# I2C_Jog_Controller.net
KiCad netlist of a schematic drawn in Altium Designer
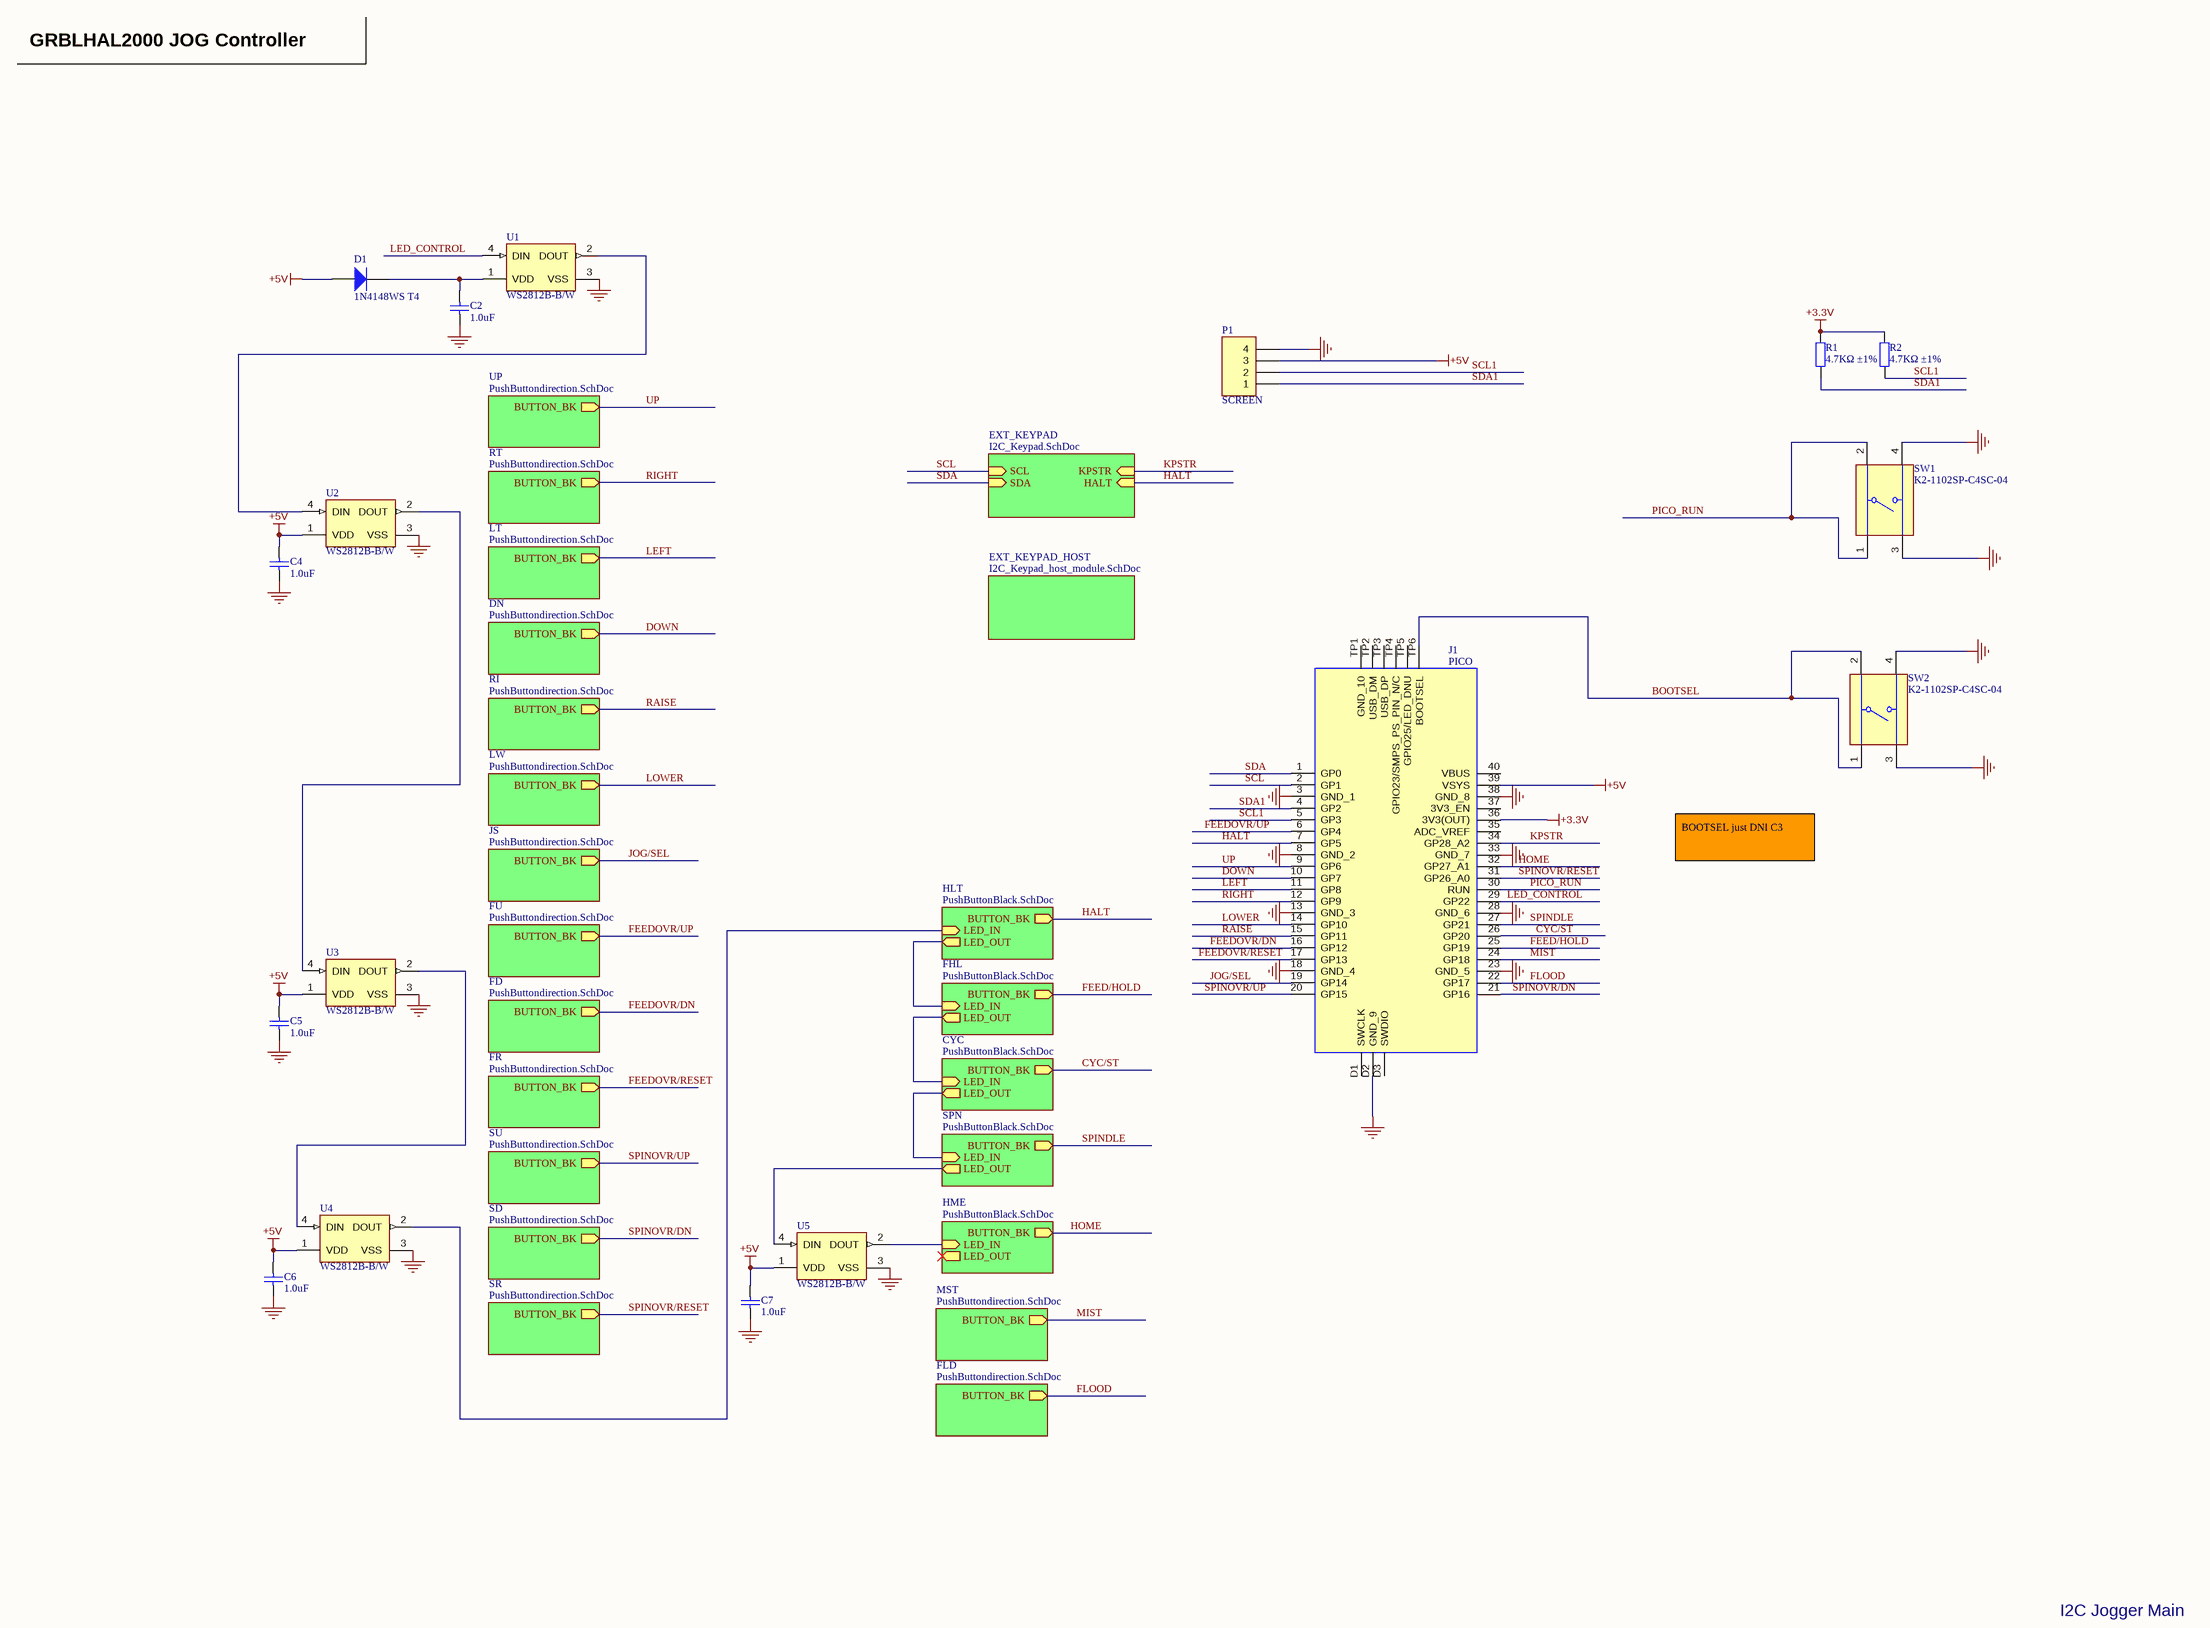
[diagram p0: I2C_Jog_Controller.SchDoc]

(export (version "E")
  (design (tool "Eeschema 10.0.6"))
  (components
    (comp (ref "C2")
      (value "1.0uF")
      (footprint "0402_C")
      (description "Chip capacitor")
      (fields
        (field (name "MANUFACTURER") "Samsung Electro-Mechanics")
        (field (name "PARTNUMBER") "CL05A105KA5NQNC")
      )
      (libsource (lib "Cap") (part "0402 1.0uF (105) 10% 25V"))
    )
    (comp (ref "C4")
      (value "1.0uF")
      (footprint "0402_C")
      (description "Chip capacitor")
      (fields
        (field (name "MANUFACTURER") "Samsung Electro-Mechanics")
        (field (name "PARTNUMBER") "CL05A105KA5NQNC")
      )
      (libsource (lib "Cap") (part "0402 1.0uF (105) 10% 25V"))
    )
    (comp (ref "C5")
      (value "1.0uF")
      (footprint "0402_C")
      (description "Chip capacitor")
      (fields
        (field (name "MANUFACTURER") "Samsung Electro-Mechanics")
        (field (name "PARTNUMBER") "CL05A105KA5NQNC")
      )
      (libsource (lib "Cap") (part "0402 1.0uF (105) 10% 25V"))
    )
    (comp (ref "C6")
      (value "1.0uF")
      (footprint "0402_C")
      (description "Chip capacitor")
      (fields
        (field (name "MANUFACTURER") "Samsung Electro-Mechanics")
        (field (name "PARTNUMBER") "CL05A105KA5NQNC")
      )
      (libsource (lib "Cap") (part "0402 1.0uF (105) 10% 25V"))
    )
    (comp (ref "C7")
      (value "1.0uF")
      (footprint "0402_C")
      (description "Chip capacitor")
      (fields
        (field (name "MANUFACTURER") "Samsung Electro-Mechanics")
        (field (name "PARTNUMBER") "CL05A105KA5NQNC")
      )
      (libsource (lib "Cap") (part "0402 1.0uF (105) 10% 25V"))
    )
    (comp (ref "D1")
      (value "1N4148WS T4")
      (footprint "SOD-323")
      (description "二极管")
      (libsource (lib "Diode") (part "SOD-323 1N4148WS T4"))
    )
    (comp (ref "J1")
      (value "PICO")
      (footprint "SamacSys:PICO")
      (description "Connector")
      (libsource (lib "I2C_Jog_Controller") (part "PICO"))
    )
    (comp (ref "P1")
      (value "SCREEN")
      (footprint "HDR1X4")
      (description "Header, 4-Pin")
      (fields (field (name "PUBLISHER") "Altium Limited"))
      (libsource (lib "Miscellaneous Connectors") (part "Header 4"))
    )
    (comp (ref "R1")
      (value "4.7KΩ ±1%")
      (footprint "0402_R")
      (description "Chip resistor")
      (fields (field (name "MANUFACTURER") "Uniroyal Elec") (field (name "PARTNUMBER") "0402WGF4701TCE"))
      (libsource (lib "RES") (part "0402 4.7K (4701) 1%"))
    )
    (comp (ref "R2")
      (value "4.7KΩ ±1%")
      (footprint "0402_R")
      (description "Chip resistor")
      (fields (field (name "MANUFACTURER") "Uniroyal Elec") (field (name "PARTNUMBER") "0402WGF4701TCE"))
      (libsource (lib "RES") (part "0402 4.7K (4701) 1%"))
    )
    (comp (ref "SW1")
      (value "K2-1102SP-C4SC-04")
      (footprint "TECO-FSM4JSMATR_V")
      (description "Top Actuated 50mA @ 12VDC Round Button SPST 6*6mm Tactile Switches ROHS")
      (libsource (lib "Altium Content Vault") (part "SW-SPST-4_A"))
    )
    (comp (ref "SW2")
      (value "K2-1102SP-C4SC-04")
      (footprint "TECO-FSM4JSMATR_V")
      (description "Top Actuated 50mA @ 12VDC Round Button SPST 6*6mm Tactile Switches ROHS")
      (libsource (lib "Altium Content Vault") (part "SW-SPST-4_A"))
    )
    (comp (ref "U1")
      (value "WS2812B-B/W")
      (footprint "ADA-RGB-1655_V")
      (fields (field (name "MANUFACTURER") "Worldsemi"))
      (libsource (lib "Altium Content Vault") (part "ADA-RGB-1655-4"))
    )
    (comp (ref "U2")
      (value "WS2812B-B/W")
      (footprint "ADA-RGB-1655_V")
      (fields (field (name "MANUFACTURER") "Worldsemi"))
      (libsource (lib "Altium Content Vault") (part "ADA-RGB-1655-4"))
    )
    (comp (ref "U3")
      (value "WS2812B-B/W")
      (footprint "ADA-RGB-1655_V")
      (fields (field (name "MANUFACTURER") "Worldsemi"))
      (libsource (lib "Altium Content Vault") (part "ADA-RGB-1655-4"))
    )
    (comp (ref "U4")
      (value "WS2812B-B/W")
      (footprint "ADA-RGB-1655_V")
      (fields (field (name "MANUFACTURER") "Worldsemi"))
      (libsource (lib "Altium Content Vault") (part "ADA-RGB-1655-4"))
    )
    (comp (ref "U5")
      (value "WS2812B-B/W")
      (footprint "ADA-RGB-1655_V")
      (fields (field (name "MANUFACTURER") "Worldsemi"))
      (libsource (lib "Altium Content Vault") (part "ADA-RGB-1655-4"))
    )
  )
  (nets
    (net (code "1") (name "+3.3V") (class "Default")
      (node (ref "J1") (pin "36") (pinfunction "3V3(OUT)_36") (pintype "passive"))
      (node (ref "R1") (pin "2") (pinfunction "2_2") (pintype "passive"))
      (node (ref "R2") (pin "2") (pinfunction "2_2") (pintype "passive"))
    )
    (net (code "2") (name "+5V") (class "Default")
      (node (ref "C4") (pin "2") (pinfunction "2_2") (pintype "passive"))
      (node (ref "C5") (pin "2") (pinfunction "2_2") (pintype "passive"))
      (node (ref "C6") (pin "2") (pinfunction "2_2") (pintype "passive"))
      (node (ref "C7") (pin "2") (pinfunction "2_2") (pintype "passive"))
      (node (ref "D1") (pin "1") (pinfunction "A_1") (pintype "passive"))
      (node (ref "J1") (pin "39") (pinfunction "VSYS_39") (pintype "passive"))
      (node (ref "P1") (pin "3") (pinfunction "3_3") (pintype "passive"))
      (node (ref "U2") (pin "1") (pinfunction "VDD_1") (pintype "power_in"))
      (node (ref "U3") (pin "1") (pinfunction "VDD_1") (pintype "power_in"))
      (node (ref "U4") (pin "1") (pinfunction "VDD_1") (pintype "power_in"))
      (node (ref "U5") (pin "1") (pinfunction "VDD_1") (pintype "power_in"))
    )
    (net (code "3") (name "/BOOTSEL") (class "Default")
      (node (ref "J1") (pin "TP6") (pinfunction "BOOTSEL_TP6") (pintype "passive"))
      (node (ref "SW2") (pin "1") (pinfunction "1_1") (pintype "passive"))
      (node (ref "SW2") (pin "2") (pinfunction "2_2") (pintype "passive"))
    )
    (net (code "4") (name "/CYC{slash}ST") (class "Default")
      (node (ref "J1") (pin "26") (pinfunction "GP20_26") (pintype "passive"))
    )
    (net (code "5") (name "/DOWN") (class "Default")
      (node (ref "J1") (pin "10") (pinfunction "GP7_10") (pintype "passive"))
    )
    (net (code "6") (name "/FEEDOVR{slash}DN") (class "Default")
      (node (ref "J1") (pin "16") (pinfunction "GP12_16") (pintype "passive"))
    )
    (net (code "7") (name "/FEEDOVR{slash}RESET") (class "Default")
      (node (ref "J1") (pin "17") (pinfunction "GP13_17") (pintype "passive"))
    )
    (net (code "8") (name "/FEEDOVR{slash}UP") (class "Default")
      (node (ref "J1") (pin "6") (pinfunction "GP4_6") (pintype "passive"))
    )
    (net (code "9") (name "/FEED{slash}HOLD") (class "Default")
      (node (ref "J1") (pin "25") (pinfunction "GP19_25") (pintype "passive"))
    )
    (net (code "10") (name "/FLOOD") (class "Default")
      (node (ref "J1") (pin "22") (pinfunction "GP17_22") (pintype "passive"))
    )
    (net (code "11") (name "/HALT") (class "Default")
      (node (ref "J1") (pin "7") (pinfunction "GP5_7") (pintype "passive"))
    )
    (net (code "12") (name "/HOME") (class "Default")
      (node (ref "J1") (pin "32") (pinfunction "GP27_A1_32") (pintype "passive"))
    )
    (net (code "13") (name "/JOG{slash}SEL") (class "Default")
      (node (ref "J1") (pin "19") (pinfunction "GP14_19") (pintype "passive"))
    )
    (net (code "14") (name "/KPSTR") (class "Default")
      (node (ref "J1") (pin "34") (pinfunction "GP28_A2_34") (pintype "passive"))
    )
    (net (code "15") (name "/LED_CONTROL") (class "Default")
      (node (ref "J1") (pin "29") (pinfunction "GP22_29") (pintype "passive"))
      (node (ref "U1") (pin "4") (pinfunction "DIN_4") (pintype "input"))
    )
    (net (code "16") (name "/LED_IN") (class "Default")
      (node (ref "U5") (pin "2") (pinfunction "DOUT_2") (pintype "output"))
    )
    (net (code "17") (name "/LED_IN_1") (class "Default")
      (node (ref "U4") (pin "2") (pinfunction "DOUT_2") (pintype "output"))
    )
    (net (code "19") (name "/LED_OUT_1") (class "Default")
      (node (ref "U5") (pin "4") (pinfunction "DIN_4") (pintype "input"))
    )
    (net (code "23") (name "/LEFT") (class "Default")
      (node (ref "J1") (pin "11") (pinfunction "GP8_11") (pintype "passive"))
    )
    (net (code "24") (name "/LOWER") (class "Default")
      (node (ref "J1") (pin "14") (pinfunction "GP10_14") (pintype "passive"))
    )
    (net (code "25") (name "/MIST") (class "Default")
      (node (ref "J1") (pin "24") (pinfunction "GP18_24") (pintype "passive"))
    )
    (net (code "26") (name "/PICO_RUN") (class "Default")
      (node (ref "J1") (pin "30") (pinfunction "RUN_30") (pintype "passive"))
      (node (ref "SW1") (pin "1") (pinfunction "1_1") (pintype "passive"))
      (node (ref "SW1") (pin "2") (pinfunction "2_2") (pintype "passive"))
    )
    (net (code "27") (name "/RAISE") (class "Default")
      (node (ref "J1") (pin "15") (pinfunction "GP11_15") (pintype "passive"))
    )
    (net (code "28") (name "/RIGHT") (class "Default")
      (node (ref "J1") (pin "12") (pinfunction "GP9_12") (pintype "passive"))
    )
    (net (code "29") (name "/SCL") (class "Default")
      (node (ref "J1") (pin "2") (pinfunction "GP1_2") (pintype "passive"))
    )
    (net (code "30") (name "/SCL1") (class "Default")
      (node (ref "J1") (pin "5") (pinfunction "GP3_5") (pintype "passive"))
      (node (ref "P1") (pin "2") (pinfunction "2_2") (pintype "passive"))
      (node (ref "R2") (pin "1") (pinfunction "1_1") (pintype "passive"))
    )
    (net (code "31") (name "/SDA") (class "Default")
      (node (ref "J1") (pin "1") (pinfunction "GP0_1") (pintype "passive"))
    )
    (net (code "32") (name "/SDA1") (class "Default")
      (node (ref "J1") (pin "4") (pinfunction "GP2_4") (pintype "passive"))
      (node (ref "P1") (pin "1") (pinfunction "1_1") (pintype "passive"))
      (node (ref "R1") (pin "1") (pinfunction "1_1") (pintype "passive"))
    )
    (net (code "33") (name "/SPINDLE") (class "Default")
      (node (ref "J1") (pin "27") (pinfunction "GP21_27") (pintype "passive"))
    )
    (net (code "34") (name "/SPINOVR{slash}DN") (class "Default")
      (node (ref "J1") (pin "21") (pinfunction "GP16_21") (pintype "passive"))
    )
    (net (code "35") (name "/SPINOVR{slash}RESET") (class "Default")
      (node (ref "J1") (pin "31") (pinfunction "GP26_A0_31") (pintype "passive"))
    )
    (net (code "36") (name "/SPINOVR{slash}UP") (class "Default")
      (node (ref "J1") (pin "20") (pinfunction "GP15_20") (pintype "passive"))
    )
    (net (code "37") (name "/UP") (class "Default")
      (node (ref "J1") (pin "9") (pinfunction "GP6_9") (pintype "passive"))
    )
    (net (code "38") (name "GND") (class "Default")
      (node (ref "C2") (pin "1") (pinfunction "1_1") (pintype "passive"))
      (node (ref "C4") (pin "1") (pinfunction "1_1") (pintype "passive"))
      (node (ref "C5") (pin "1") (pinfunction "1_1") (pintype "passive"))
      (node (ref "C6") (pin "1") (pinfunction "1_1") (pintype "passive"))
      (node (ref "C7") (pin "1") (pinfunction "1_1") (pintype "passive"))
      (node (ref "J1") (pin "13") (pinfunction "GND_3_13") (pintype "passive"))
      (node (ref "J1") (pin "18") (pinfunction "GND_4_18") (pintype "passive"))
      (node (ref "J1") (pin "23") (pinfunction "GND_5_23") (pintype "passive"))
      (node (ref "J1") (pin "28") (pinfunction "GND_6_28") (pintype "passive"))
      (node (ref "J1") (pin "3") (pinfunction "GND_1_3") (pintype "passive"))
      (node (ref "J1") (pin "33") (pinfunction "GND_7_33") (pintype "passive"))
      (node (ref "J1") (pin "38") (pinfunction "GND_8_38") (pintype "passive"))
      (node (ref "J1") (pin "8") (pinfunction "GND_2_8") (pintype "passive"))
      (node (ref "J1") (pin "D2") (pinfunction "GND_9_D2") (pintype "passive"))
      (node (ref "P1") (pin "4") (pinfunction "4_4") (pintype "passive"))
      (node (ref "SW1") (pin "3") (pinfunction "3_3") (pintype "passive"))
      (node (ref "SW1") (pin "4") (pinfunction "4_4") (pintype "passive"))
      (node (ref "SW2") (pin "3") (pinfunction "3_3") (pintype "passive"))
      (node (ref "SW2") (pin "4") (pinfunction "4_4") (pintype "passive"))
      (node (ref "U1") (pin "3") (pinfunction "VSS_3") (pintype "power_in"))
      (node (ref "U2") (pin "3") (pinfunction "VSS_3") (pintype "power_in"))
      (node (ref "U3") (pin "3") (pinfunction "VSS_3") (pintype "power_in"))
      (node (ref "U4") (pin "3") (pinfunction "VSS_3") (pintype "power_in"))
      (node (ref "U5") (pin "3") (pinfunction "VSS_3") (pintype "power_in"))
    )
    (net (code "39") (name "Net-(D1-K)") (class "Default")
      (node (ref "C2") (pin "2") (pinfunction "2_2") (pintype "passive"))
      (node (ref "D1") (pin "2") (pinfunction "K_2") (pintype "passive"))
      (node (ref "U1") (pin "1") (pinfunction "VDD_1") (pintype "power_in"))
    )
    (net (code "40") (name "Net-(U1-DOUT)") (class "Default")
      (node (ref "U1") (pin "2") (pinfunction "DOUT_2") (pintype "output"))
      (node (ref "U2") (pin "4") (pinfunction "DIN_4") (pintype "input"))
    )
    (net (code "41") (name "Net-(U2-DOUT)") (class "Default")
      (node (ref "U2") (pin "2") (pinfunction "DOUT_2") (pintype "output"))
      (node (ref "U3") (pin "4") (pinfunction "DIN_4") (pintype "input"))
    )
    (net (code "42") (name "Net-(U3-DOUT)") (class "Default")
      (node (ref "U3") (pin "2") (pinfunction "DOUT_2") (pintype "output"))
      (node (ref "U4") (pin "4") (pinfunction "DIN_4") (pintype "input"))
    )
    (net (code "43") (name "unconnected-(J1-3V3_EN-Pad37)") (class "Default")
      (node (ref "J1") (pin "37") (pinfunction "3V3_EN_37") (pintype "passive"))
    )
    (net (code "44") (name "unconnected-(J1-ADC_VREF-Pad35)") (class "Default")
      (node (ref "J1") (pin "35") (pinfunction "ADC_VREF_35") (pintype "passive"))
    )
    (net (code "45") (name "unconnected-(J1-GND_10-PadTP1)") (class "Default")
      (node (ref "J1") (pin "TP1") (pinfunction "GND_10_TP1") (pintype "passive"))
    )
    (net (code "46") (name "unconnected-(J1-GPIO23{slash}SMPS_PS_PIN_N{slash}C-PadTP4)") (class "Default")
      (node (ref "J1") (pin "TP4") (pinfunction "GPIO23/SMPS_PS_PIN_N/C_TP4") (pintype "passive"))
    )
    (net (code "47") (name "unconnected-(J1-GPIO25{slash}LED_DNU-PadTP5)") (class "Default")
      (node (ref "J1") (pin "TP5") (pinfunction "GPIO25/LED_DNU_TP5") (pintype "passive"))
    )
    (net (code "48") (name "unconnected-(J1-SWCLK-PadD1)") (class "Default")
      (node (ref "J1") (pin "D1") (pinfunction "SWCLK_D1") (pintype "passive"))
    )
    (net (code "49") (name "unconnected-(J1-SWDIO-PadD3)") (class "Default")
      (node (ref "J1") (pin "D3") (pinfunction "SWDIO_D3") (pintype "passive"))
    )
    (net (code "50") (name "unconnected-(J1-USB_DM-PadTP2)") (class "Default")
      (node (ref "J1") (pin "TP2") (pinfunction "USB_DM_TP2") (pintype "passive"))
    )
    (net (code "51") (name "unconnected-(J1-USB_DP-PadTP3)") (class "Default")
      (node (ref "J1") (pin "TP3") (pinfunction "USB_DP_TP3") (pintype "passive"))
    )
    (net (code "52") (name "unconnected-(J1-VBUS-Pad40)") (class "Default")
      (node (ref "J1") (pin "40") (pinfunction "VBUS_40") (pintype "passive"))
    )
  )
)
